# 09_Misc.net
KiCad netlist of a schematic drawn in Altium Designer
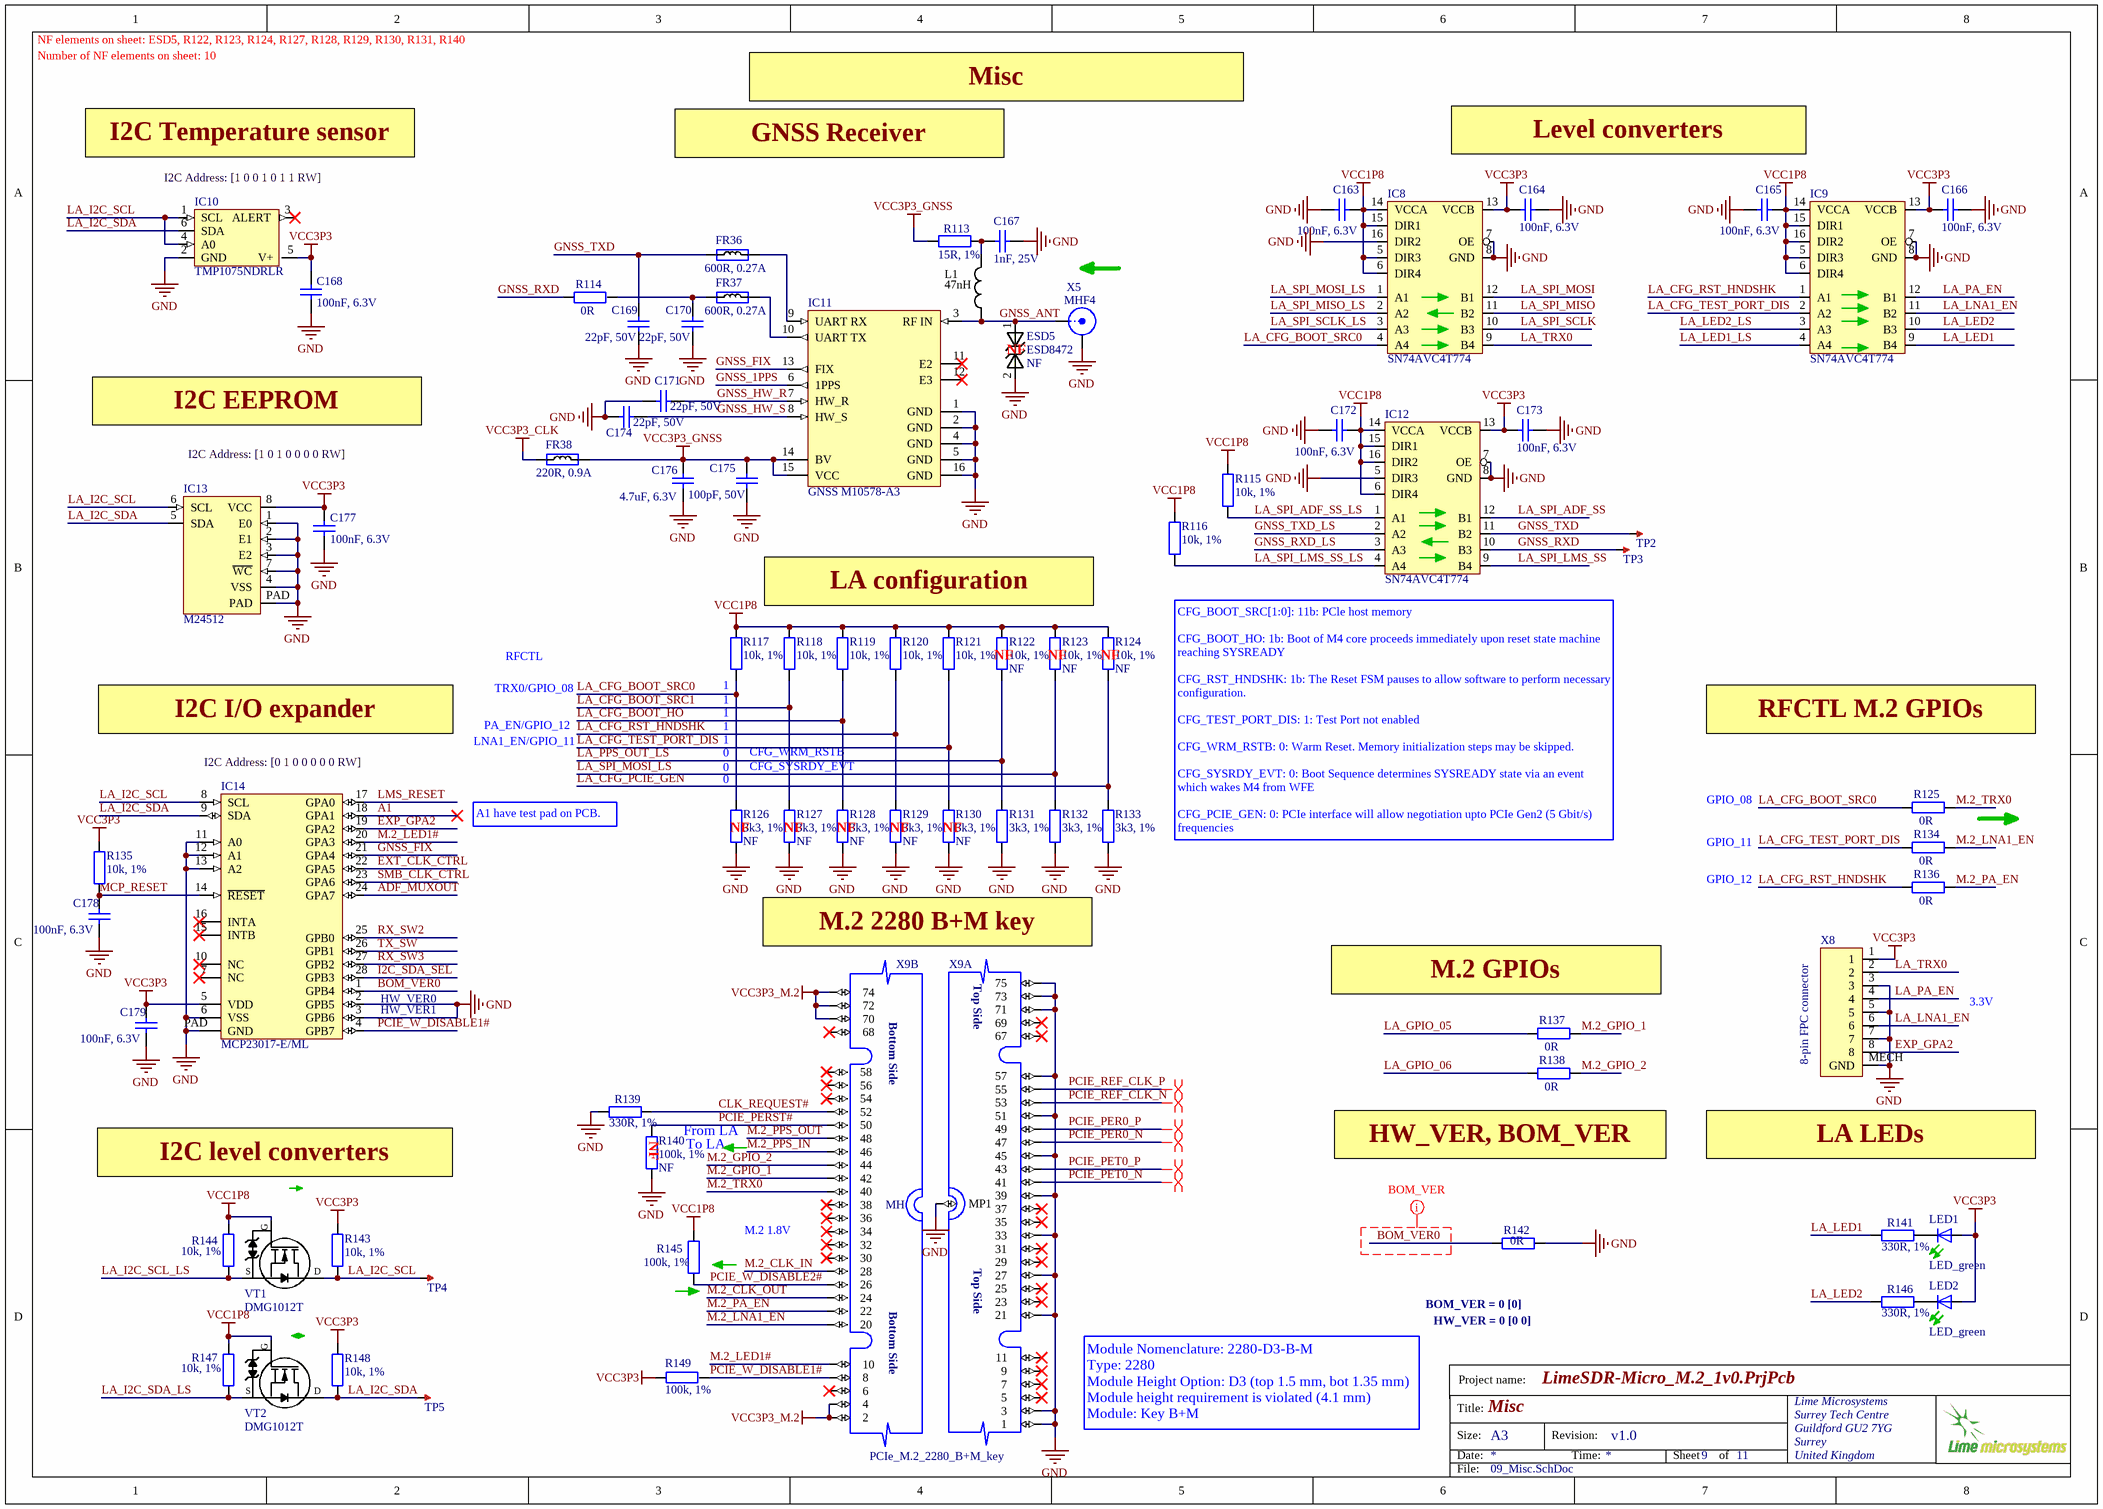
[diagram p0: 09_Misc.SchDoc]

(export (version "E")
  (design (tool "Eeschema 10.0.6"))
  (components
    (comp (ref "C163")
      (value "100nF, 6.3V")
      (footprint "CAP0201")
      (fields (field (name "MANUFACTURER") "Samsung") (field (name "TOLERANCE") "20%"))
      (libsource (lib "LimeMicroAltiumLib_schLib") (part "Cap_0402"))
    )
    (comp (ref "C164")
      (value "100nF, 6.3V")
      (footprint "CAP0201")
      (fields (field (name "MANUFACTURER") "Samsung") (field (name "TOLERANCE") "20%"))
      (libsource (lib "LimeMicroAltiumLib_schLib") (part "Cap_0402"))
    )
    (comp (ref "C165")
      (value "100nF, 6.3V")
      (footprint "CAP0201")
      (fields (field (name "MANUFACTURER") "Samsung") (field (name "TOLERANCE") "20%"))
      (libsource (lib "LimeMicroAltiumLib_schLib") (part "Cap_0402"))
    )
    (comp (ref "C166")
      (value "100nF, 6.3V")
      (footprint "CAP0201")
      (fields (field (name "MANUFACTURER") "Samsung") (field (name "TOLERANCE") "20%"))
      (libsource (lib "LimeMicroAltiumLib_schLib") (part "Cap_0402"))
    )
    (comp (ref "C167")
      (value "1nF, 25V")
      (footprint "CAP0201")
      (fields (field (name "TOLERANCE") "±10%") (field (name "MANUFACTURER") "TDK Corporation"))
      (libsource (lib "LimeMicroAltiumLib_schLib") (part "Cap_0402"))
    )
    (comp (ref "C168")
      (value "100nF, 6.3V")
      (footprint "CAP0201")
      (fields (field (name "MANUFACTURER") "Samsung") (field (name "TOLERANCE") "20%"))
      (libsource (lib "LimeMicroAltiumLib_schLib") (part "Cap_0402"))
    )
    (comp (ref "C169")
      (value "22pF, 50V")
      (footprint "CAP0201")
      (fields
        (field (name "MANUFACTURER") "Murata")
        (field (name "TOLERANCE") "5%")
        (field (name "VOLTAGE") "50V")
      )
      (libsource (lib "LimeMicroAltiumLib_schLib") (part "Cap_0402"))
    )
    (comp (ref "C170")
      (value "22pF, 50V")
      (footprint "CAP0201")
      (fields
        (field (name "MANUFACTURER") "Murata")
        (field (name "TOLERANCE") "5%")
        (field (name "VOLTAGE") "50V")
      )
      (libsource (lib "LimeMicroAltiumLib_schLib") (part "Cap_0402"))
    )
    (comp (ref "C171")
      (value "22pF, 50V")
      (footprint "CAP0201")
      (fields
        (field (name "MANUFACTURER") "Murata")
        (field (name "TOLERANCE") "5%")
        (field (name "VOLTAGE") "50V")
      )
      (libsource (lib "LimeMicroAltiumLib_schLib") (part "Cap_0402"))
    )
    (comp (ref "C172")
      (value "100nF, 6.3V")
      (footprint "CAP0201")
      (fields (field (name "MANUFACTURER") "Samsung") (field (name "TOLERANCE") "20%"))
      (libsource (lib "LimeMicroAltiumLib_schLib") (part "Cap_0402"))
    )
    (comp (ref "C173")
      (value "100nF, 6.3V")
      (footprint "CAP0201")
      (fields (field (name "MANUFACTURER") "Samsung") (field (name "TOLERANCE") "20%"))
      (libsource (lib "LimeMicroAltiumLib_schLib") (part "Cap_0402"))
    )
    (comp (ref "C174")
      (value "22pF, 50V")
      (footprint "CAP0201")
      (fields
        (field (name "MANUFACTURER") "Murata")
        (field (name "TOLERANCE") "5%")
        (field (name "VOLTAGE") "50V")
      )
      (libsource (lib "LimeMicroAltiumLib_schLib") (part "Cap_0402"))
    )
    (comp (ref "C175")
      (value "100pF, 50V")
      (footprint "CAP0201")
      (fields
        (field (name "MANUFACTURER") "TDK")
        (field (name "TOLERANCE") "5%")
        (field (name "VOLTAGE") "50V")
      )
      (libsource (lib "LimeMicroAltiumLib_schLib") (part "Cap_0402"))
    )
    (comp (ref "C176")
      (value "4.7uF, 6.3V")
      (footprint "CAP0402")
      (fields
        (field (name "MANUFACTURER") "Murata Electronics North America")
        (field (name "TOLERANCE") "±20%")
      )
      (libsource (lib "LimeMicroAltiumLib_schLib") (part "Cap_0402"))
    )
    (comp (ref "C177")
      (value "100nF, 6.3V")
      (footprint "CAP0201")
      (fields (field (name "MANUFACTURER") "Samsung") (field (name "TOLERANCE") "20%"))
      (libsource (lib "LimeMicroAltiumLib_schLib") (part "Cap_0402"))
    )
    (comp (ref "C178")
      (value "100nF, 6.3V")
      (footprint "CAP0201")
      (fields (field (name "MANUFACTURER") "Samsung") (field (name "TOLERANCE") "20%"))
      (libsource (lib "LimeMicroAltiumLib_schLib") (part "Cap_0402"))
    )
    (comp (ref "C179")
      (value "100nF, 6.3V")
      (footprint "CAP0201")
      (fields (field (name "MANUFACTURER") "Samsung") (field (name "TOLERANCE") "20%"))
      (libsource (lib "LimeMicroAltiumLib_schLib") (part "Cap_0402"))
    )
    (comp (ref "ESD5")
      (value "ESD8472")
      (footprint "ESD8472_X3DFN2")
      (fields (field (name "MANUFACTURER") "ON Semiconductor") (field (name "ASSEMBLY INFO") "NF"))
      (libsource (lib "LimeMicroAltiumLib_schLib") (part "ESD8472"))
    )
    (comp (ref "FR36")
      (value "600R, 0.27A")
      (footprint "RES0201")
      (fields (field (name "MANUFACTURER") "Taiyo Yuden"))
      (libsource (lib "LimeMicroAltiumLib_schLib") (part "Ferrite"))
    )
    (comp (ref "FR37")
      (value "600R, 0.27A")
      (footprint "RES0201")
      (fields (field (name "MANUFACTURER") "Taiyo Yuden"))
      (libsource (lib "LimeMicroAltiumLib_schLib") (part "Ferrite"))
    )
    (comp (ref "FR38")
      (value "220R, 0.9A")
      (footprint "RES0402")
      (fields (field (name "MANUFACTURER") "TDK Corporation"))
      (libsource (lib "LimeFPGAboard_schLib") (part "Ferrite"))
    )
    (comp (ref "IC8")
      (value "SN74AVC4T774")
      (footprint "SN74AVC4T774_v1")
      (fields (field (name "MANUFACTURER") "Texas Instruments"))
      (libsource (lib "LimeMicroAltiumLib") (part "SN74AVC4T774"))
    )
    (comp (ref "IC9")
      (value "SN74AVC4T774")
      (footprint "SN74AVC4T774_v1")
      (fields (field (name "MANUFACTURER") "Texas Instruments"))
      (libsource (lib "LimeMicroAltiumLib") (part "SN74AVC4T774"))
    )
    (comp (ref "IC10")
      (value "TMP1075NDRLR")
      (footprint "TMP1075NDRLR_temperature_sensor_SOT563")
      (fields (field (name "MANUFACTURER") "Texas Instruments"))
      (libsource (lib "LimeMicroAltiumLib_schLib_r04") (part "TMP1075NDRLR_temperature_sensor"))
    )
    (comp (ref "IC11")
      (value "GNSS M10578-A3")
      (footprint "M10578-A3_v2")
      (fields (field (name "MANUFACTURER") "Antenova"))
      (libsource (lib "LimeMicroAltiumLib_schLib_r04") (part "M10578-A3_GPS_GNSS"))
    )
    (comp (ref "IC12")
      (value "SN74AVC4T774")
      (footprint "SN74AVC4T774_v1")
      (fields (field (name "MANUFACTURER") "Texas Instruments"))
      (libsource (lib "LimeMicroAltiumLib") (part "SN74AVC4T774"))
    )
    (comp (ref "IC13")
      (value "M24512")
      (footprint "M24128-DFMC6TG")
      (fields (field (name "MANUFACTURER") "STMicroelectronics"))
      (libsource (lib "LimeMicroAltiumLib_schLib") (part "M24128-DFMC6TG"))
    )
    (comp (ref "IC14")
      (value "MCP23017-E/ML")
      (footprint "MCP23017-E/ML_QFN28")
      (fields (field (name "MANUFACTURER") "Microchip"))
      (libsource (lib "LimeMicroAltiumLib") (part "MCP23017-E/ML_I2C_expander"))
    )
    (comp (ref "L1")
      (value "47nH")
      (footprint "RES0402")
      (fields
        (field (name "MANUFACTURER") "COILCRAFT")
        (field (name "MANUFACTURER PART NUMBER") "0402HP-47NXJLU")
      )
      (libsource (lib "LimeMicroAltiumLib_schLib") (part "Inductor_0603"))
    )
    (comp (ref "LED1")
      (value "LED_green")
      (footprint "LED0201")
      (fields (field (name "MANUFACTURER") "Kingbright"))
      (libsource (lib "LimeFPGAboard_schLib") (part "LED_green"))
    )
    (comp (ref "LED2")
      (value "LED_green")
      (footprint "LED0201")
      (fields (field (name "MANUFACTURER") "Kingbright"))
      (libsource (lib "LimeFPGAboard_schLib") (part "LED_green"))
    )
    (comp (ref "R113")
      (value "15R, 1%")
      (footprint "RES0201")
      (fields (field (name "MANUFACTURER") "Yageo") (field (name "TOLERANCE") "1%"))
      (libsource (lib "LimeFPGAboard_schLib") (part "Res_0402"))
    )
    (comp (ref "R114")
      (value "0R")
      (footprint "RES0201")
      (fields (field (name "MANUFACTURER") "Yageo") (field (name "TOLERANCE") "5%"))
      (libsource (lib "LimeFPGAboard_schLib") (part "Res_0402"))
    )
    (comp (ref "R115")
      (value "10k, 1%")
      (footprint "RES0201")
      (fields (field (name "MANUFACTURER") "Yageo") (field (name "TOLERANCE") "1%"))
      (libsource (lib "LimeFPGAboard_schLib") (part "Res_0402"))
    )
    (comp (ref "R116")
      (value "10k, 1%")
      (footprint "RES0201")
      (fields (field (name "MANUFACTURER") "Yageo") (field (name "TOLERANCE") "1%"))
      (libsource (lib "LimeFPGAboard_schLib") (part "Res_0402"))
    )
    (comp (ref "R117")
      (value "10k, 1%")
      (footprint "RES0201")
      (fields (field (name "MANUFACTURER") "Yageo") (field (name "TOLERANCE") "1%"))
      (libsource (lib "LimeFPGAboard_schLib") (part "Res_0402"))
    )
    (comp (ref "R118")
      (value "10k, 1%")
      (footprint "RES0201")
      (fields (field (name "MANUFACTURER") "Yageo") (field (name "TOLERANCE") "1%"))
      (libsource (lib "LimeFPGAboard_schLib") (part "Res_0402"))
    )
    (comp (ref "R119")
      (value "10k, 1%")
      (footprint "RES0201")
      (fields (field (name "MANUFACTURER") "Yageo") (field (name "TOLERANCE") "1%"))
      (libsource (lib "LimeFPGAboard_schLib") (part "Res_0402"))
    )
    (comp (ref "R120")
      (value "10k, 1%")
      (footprint "RES0201")
      (fields (field (name "MANUFACTURER") "Yageo") (field (name "TOLERANCE") "1%"))
      (libsource (lib "LimeFPGAboard_schLib") (part "Res_0402"))
    )
    (comp (ref "R121")
      (value "10k, 1%")
      (footprint "RES0201")
      (fields (field (name "MANUFACTURER") "Yageo") (field (name "TOLERANCE") "1%"))
      (libsource (lib "LimeFPGAboard_schLib") (part "Res_0402"))
    )
    (comp (ref "R122")
      (value "10k, 1%")
      (footprint "RES0201")
      (fields
        (field (name "ASSEMBLY INFO") "NF")
        (field (name "MANUFACTURER") "Yageo")
        (field (name "TOLERANCE") "1%")
      )
      (libsource (lib "LimeFPGAboard_schLib") (part "Res_0402"))
    )
    (comp (ref "R123")
      (value "10k, 1%")
      (footprint "RES0201")
      (fields
        (field (name "ASSEMBLY INFO") "NF")
        (field (name "MANUFACTURER") "Yageo")
        (field (name "TOLERANCE") "1%")
      )
      (libsource (lib "LimeFPGAboard_schLib") (part "Res_0402"))
    )
    (comp (ref "R124")
      (value "10k, 1%")
      (footprint "RES0201")
      (fields
        (field (name "ASSEMBLY INFO") "NF")
        (field (name "MANUFACTURER") "Yageo")
        (field (name "TOLERANCE") "1%")
      )
      (libsource (lib "LimeFPGAboard_schLib") (part "Res_0402"))
    )
    (comp (ref "R125")
      (value "0R")
      (footprint "RES0201")
      (fields (field (name "MANUFACTURER") "Yageo") (field (name "TOLERANCE") "5%"))
      (libsource (lib "LimeFPGAboard_schLib") (part "Res_0402"))
    )
    (comp (ref "R126")
      (value "3k3, 1%")
      (footprint "RES0201")
      (fields
        (field (name "ASSEMBLY INFO") "NF")
        (field (name "MANUFACTURER") "Yageo")
        (field (name "TOLERANCE") "1%")
      )
      (libsource (lib "LimeFPGAboard_schLib") (part "Res_0402"))
    )
    (comp (ref "R127")
      (value "3k3, 1%")
      (footprint "RES0201")
      (fields
        (field (name "ASSEMBLY INFO") "NF")
        (field (name "MANUFACTURER") "Yageo")
        (field (name "TOLERANCE") "1%")
      )
      (libsource (lib "LimeFPGAboard_schLib") (part "Res_0402"))
    )
    (comp (ref "R128")
      (value "3k3, 1%")
      (footprint "RES0201")
      (fields
        (field (name "ASSEMBLY INFO") "NF")
        (field (name "MANUFACTURER") "Yageo")
        (field (name "TOLERANCE") "1%")
      )
      (libsource (lib "LimeFPGAboard_schLib") (part "Res_0402"))
    )
    (comp (ref "R129")
      (value "3k3, 1%")
      (footprint "RES0201")
      (fields
        (field (name "ASSEMBLY INFO") "NF")
        (field (name "MANUFACTURER") "Yageo")
        (field (name "TOLERANCE") "1%")
      )
      (libsource (lib "LimeFPGAboard_schLib") (part "Res_0402"))
    )
    (comp (ref "R130")
      (value "3k3, 1%")
      (footprint "RES0201")
      (fields
        (field (name "ASSEMBLY INFO") "NF")
        (field (name "MANUFACTURER") "Yageo")
        (field (name "TOLERANCE") "1%")
      )
      (libsource (lib "LimeFPGAboard_schLib") (part "Res_0402"))
    )
    (comp (ref "R131")
      (value "3k3, 1%")
      (footprint "RES0201")
      (fields (field (name "MANUFACTURER") "Yageo") (field (name "TOLERANCE") "1%"))
      (libsource (lib "LimeFPGAboard_schLib") (part "Res_0402"))
    )
    (comp (ref "R132")
      (value "3k3, 1%")
      (footprint "RES0201")
      (fields (field (name "MANUFACTURER") "Yageo") (field (name "TOLERANCE") "1%"))
      (libsource (lib "LimeFPGAboard_schLib") (part "Res_0402"))
    )
    (comp (ref "R133")
      (value "3k3, 1%")
      (footprint "RES0201")
      (fields (field (name "MANUFACTURER") "Yageo") (field (name "TOLERANCE") "1%"))
      (libsource (lib "LimeFPGAboard_schLib") (part "Res_0402"))
    )
    (comp (ref "R134")
      (value "0R")
      (footprint "RES0201")
      (fields (field (name "MANUFACTURER") "Yageo") (field (name "TOLERANCE") "5%"))
      (libsource (lib "LimeFPGAboard_schLib") (part "Res_0402"))
    )
    (comp (ref "R135")
      (value "10k, 1%")
      (footprint "RES0201")
      (fields (field (name "MANUFACTURER") "Yageo") (field (name "TOLERANCE") "1%"))
      (libsource (lib "LimeFPGAboard_schLib") (part "Res_0402"))
    )
    (comp (ref "R136")
      (value "0R")
      (footprint "RES0201")
      (fields (field (name "MANUFACTURER") "Yageo") (field (name "TOLERANCE") "5%"))
      (libsource (lib "LimeFPGAboard_schLib") (part "Res_0402"))
    )
    (comp (ref "R137")
      (value "0R")
      (footprint "RES0201")
      (fields (field (name "MANUFACTURER") "Yageo") (field (name "TOLERANCE") "5%"))
      (libsource (lib "LimeFPGAboard_schLib") (part "Res_0402"))
    )
    (comp (ref "R138")
      (value "0R")
      (footprint "RES0201")
      (fields (field (name "MANUFACTURER") "Yageo") (field (name "TOLERANCE") "5%"))
      (libsource (lib "LimeFPGAboard_schLib") (part "Res_0402"))
    )
    (comp (ref "R139")
      (value "330R, 1%")
      (footprint "RES0201")
      (fields (field (name "MANUFACTURER") "Vishay Dale") (field (name "TOLERANCE") "1%"))
      (libsource (lib "LimeFPGAboard_schLib") (part "Res_0402"))
    )
    (comp (ref "R140")
      (value "100k, 1%")
      (footprint "RES0201")
      (fields
        (field (name "ASSEMBLY INFO") "NF")
        (field (name "MANUFACTURER") "Yageo")
        (field (name "TOLERANCE") "1%")
      )
      (libsource (lib "LimeMicroAltiumLib_schLib") (part "Res_0402"))
    )
    (comp (ref "R141")
      (value "330R, 1%")
      (footprint "RES0201")
      (fields (field (name "MANUFACTURER") "Vishay Dale") (field (name "TOLERANCE") "1%"))
      (libsource (lib "LimeFPGAboard_schLib") (part "Res_0402"))
    )
    (comp (ref "R142")
      (value "0R")
      (footprint "RES0201")
      (fields (field (name "MANUFACTURER") "Yageo") (field (name "TOLERANCE") "5%"))
      (libsource (lib "LimeFPGAboard_schLib") (part "Res_0402"))
    )
    (comp (ref "R143")
      (value "10k, 1%")
      (footprint "RES0201")
      (fields (field (name "MANUFACTURER") "Yageo") (field (name "TOLERANCE") "1%"))
      (libsource (lib "LimeFPGAboard_schLib") (part "Res_0402"))
    )
    (comp (ref "R144")
      (value "10k, 1%")
      (footprint "RES0201")
      (fields (field (name "MANUFACTURER") "Yageo") (field (name "TOLERANCE") "1%"))
      (libsource (lib "LimeFPGAboard_schLib") (part "Res_0402"))
    )
    (comp (ref "R145")
      (value "100k, 1%")
      (footprint "RES0201")
      (fields (field (name "MANUFACTURER") "Yageo") (field (name "TOLERANCE") "1%"))
      (libsource (lib "LimeMicroAltiumLib_schLib") (part "Res_0402"))
    )
    (comp (ref "R146")
      (value "330R, 1%")
      (footprint "RES0201")
      (fields (field (name "MANUFACTURER") "Vishay Dale") (field (name "TOLERANCE") "1%"))
      (libsource (lib "LimeFPGAboard_schLib") (part "Res_0402"))
    )
    (comp (ref "R147")
      (value "10k, 1%")
      (footprint "RES0201")
      (fields (field (name "MANUFACTURER") "Yageo") (field (name "TOLERANCE") "1%"))
      (libsource (lib "LimeFPGAboard_schLib") (part "Res_0402"))
    )
    (comp (ref "R148")
      (value "10k, 1%")
      (footprint "RES0201")
      (fields (field (name "MANUFACTURER") "Yageo") (field (name "TOLERANCE") "1%"))
      (libsource (lib "LimeFPGAboard_schLib") (part "Res_0402"))
    )
    (comp (ref "R149")
      (value "100k, 1%")
      (footprint "RES0201")
      (fields (field (name "MANUFACTURER") "Yageo") (field (name "TOLERANCE") "1%"))
      (libsource (lib "LimeMicroAltiumLib_schLib") (part "Res_0402"))
    )
    (comp (ref "TP2")
      (value "TESTPOINT_PAD")
      (footprint "TP_PAD_1MM")
      (description "Test Point PCB mount Miniature White")
      (libsource (lib "LimeMicroAltiumLib_schLib_r04") (part "TESTPOINT_PAD"))
    )
    (comp (ref "TP3")
      (value "TESTPOINT_PAD")
      (footprint "TP_PAD_1MM")
      (description "Test Point PCB mount Miniature White")
      (libsource (lib "LimeMicroAltiumLib_schLib_r04") (part "TESTPOINT_PAD"))
    )
    (comp (ref "TP4")
      (value "TESTPOINT_PAD")
      (footprint "TP_PAD_1MM")
      (description "Test Point PCB mount Miniature White")
      (libsource (lib "LimeMicroAltiumLib_schLib_r04") (part "TESTPOINT_PAD"))
    )
    (comp (ref "TP5")
      (value "TESTPOINT_PAD")
      (footprint "TP_PAD_1MM")
      (description "Test Point PCB mount Miniature White")
      (libsource (lib "LimeMicroAltiumLib_schLib_r04") (part "TESTPOINT_PAD"))
    )
    (comp (ref "VT1")
      (value "DMG1012T")
      (footprint "SOT523")
      (fields (field (name "MANUFACTURER") "Diodes Incorporated"))
      (libsource (lib "LimeMicroAltiumLib_schLib_r01") (part "DMG1012T"))
    )
    (comp (ref "VT2")
      (value "DMG1012T")
      (footprint "SOT523")
      (fields (field (name "MANUFACTURER") "Diodes Incorporated"))
      (libsource (lib "LimeMicroAltiumLib_schLib_r01") (part "DMG1012T"))
    )
    (comp (ref "X5")
      (value "MHF4")
      (footprint "IPEX_MHF4_conn")
      (description "IPEX MHF4 Connector Jack, Male Pin 50 Ohms Surface Mount Solder")
      (fields (field (name "MANUFACTURER") "TE Connectivity / Linx Technologies"))
      (libsource (lib "LimeMicroAltiumLib_schLib") (part "RF_IF_connector"))
    )
    (comp (ref "X8")
      (value "8-pin FPC connector")
      (footprint "503480-0800_8PIN_FPC_CONN")
      (fields (field (name "MANUFACTURER") "Molex"))
      (libsource (lib "LimeMicroAltiumLib_schLib_r04") (part "503480-0800_8PIN_FPC_CONN"))
    )
    (comp (ref "X9")
      (value "PCIe_M.2_2280_B+M_key")
      (footprint "PCIe_M.2_2280_B+M_key")
      (libsource (lib "LimeMicroAltiumLib") (part "PCIe_M.2_2280_B+M_key"))
    )
  )
  (nets
    (net (code "1") (name "/A1") (class "Default")
      (node (ref "IC14") (pin "18") (pinfunction "GPA1_18") (pintype "bidirectional+no_connect"))
    )
    (net (code "2") (name "/ADF_MUXOUT") (class "Default")
      (node (ref "IC14") (pin "24") (pinfunction "GPA7_24") (pintype "bidirectional"))
    )
    (net (code "3") (name "/BOM_VER0") (class "Default")
      (node (ref "IC14") (pin "1") (pinfunction "GPB4_1") (pintype "bidirectional"))
      (node (ref "R142") (pin "1") (pinfunction "1_1") (pintype "passive"))
    )
    (net (code "4") (name "/CLK_REQUEST#") (class "Default")
      (node (ref "R139") (pin "1") (pinfunction "1_1") (pintype "passive"))
      (node (ref "X9") (pin "P52") (pinfunction "52_P52") (pintype "bidirectional"))
    )
    (net (code "5") (name "/EXP_GPA2") (class "Default")
      (node (ref "IC14") (pin "19") (pinfunction "GPA2_19") (pintype "bidirectional"))
      (node (ref "X8") (pin "8") (pinfunction "8_8") (pintype "passive"))
    )
    (net (code "6") (name "/EXT_CLK_CTRL") (class "Default")
      (node (ref "IC14") (pin "22") (pinfunction "GPA5_22") (pintype "bidirectional"))
    )
    (net (code "7") (name "/GNSS_1PPS") (class "Default")
      (node (ref "IC11") (pin "6") (pinfunction "1PPS_6") (pintype "output"))
    )
    (net (code "8") (name "/GNSS_ANT") (class "Default")
      (node (ref "ESD5") (pin "1") (pinfunction "1_1") (pintype "passive"))
      (node (ref "IC11") (pin "3") (pinfunction "RF_IN_3") (pintype "input"))
      (node (ref "L1") (pin "1") (pinfunction "1_1") (pintype "passive"))
      (node (ref "X5") (pin "1") (pinfunction "X_1") (pintype "passive"))
    )
    (net (code "9") (name "/GNSS_FIX") (class "Default")
      (node (ref "IC11") (pin "13") (pinfunction "FIX_13") (pintype "output"))
      (node (ref "IC14") (pin "21") (pinfunction "GPA4_21") (pintype "bidirectional"))
    )
    (net (code "10") (name "/GNSS_HW_R") (class "Default")
      (node (ref "C171") (pin "1") (pinfunction "1_1") (pintype "passive"))
      (node (ref "IC11") (pin "7") (pinfunction "HW_R_7") (pintype "input"))
    )
    (net (code "11") (name "/GNSS_HW_S") (class "Default")
      (node (ref "C174") (pin "1") (pinfunction "1_1") (pintype "passive"))
      (node (ref "IC11") (pin "8") (pinfunction "HW_S_8") (pintype "input"))
    )
    (net (code "12") (name "/GNSS_RXD") (class "Default")
      (node (ref "IC12") (pin "10") (pinfunction "B3_10") (pintype "passive"))
      (node (ref "R114") (pin "1") (pinfunction "1_1") (pintype "passive"))
      (node (ref "TP3") (pin "1") (pintype "passive"))
    )
    (net (code "13") (name "/GNSS_RXD_LS") (class "Default")
      (node (ref "IC12") (pin "3") (pinfunction "A3_3") (pintype "passive"))
    )
    (net (code "14") (name "/GNSS_TXD") (class "Default")
      (node (ref "C169") (pin "1") (pinfunction "1_1") (pintype "passive"))
      (node (ref "FR36") (pin "1") (pinfunction "1_1") (pintype "passive"))
      (node (ref "IC12") (pin "11") (pinfunction "B2_11") (pintype "passive"))
      (node (ref "TP2") (pin "1") (pintype "passive"))
    )
    (net (code "15") (name "/GNSS_TXD_LS") (class "Default")
      (node (ref "IC12") (pin "2") (pinfunction "A2_2") (pintype "passive"))
    )
    (net (code "16") (name "/I2C_SDA_SEL") (class "Default")
      (node (ref "IC14") (pin "28") (pinfunction "GPB3_28") (pintype "bidirectional"))
    )
    (net (code "17") (name "/LA_CFG_BOOT_HO") (class "Default")
      (node (ref "R119") (pin "2") (pinfunction "2_2") (pintype "passive"))
      (node (ref "R128") (pin "1") (pinfunction "1_1") (pintype "passive"))
    )
    (net (code "18") (name "/LA_CFG_BOOT_SRC0") (class "Default")
      (node (ref "IC8") (pin "4") (pinfunction "A4_4") (pintype "passive"))
      (node (ref "R117") (pin "2") (pinfunction "2_2") (pintype "passive"))
      (node (ref "R125") (pin "1") (pinfunction "1_1") (pintype "passive"))
      (node (ref "R126") (pin "1") (pinfunction "1_1") (pintype "passive"))
    )
    (net (code "19") (name "/LA_CFG_BOOT_SRC1") (class "Default")
      (node (ref "R118") (pin "2") (pinfunction "2_2") (pintype "passive"))
      (node (ref "R127") (pin "1") (pinfunction "1_1") (pintype "passive"))
    )
    (net (code "20") (name "/LA_CFG_PCIE_GEN") (class "Default")
      (node (ref "R124") (pin "2") (pinfunction "2_2") (pintype "passive"))
      (node (ref "R133") (pin "1") (pinfunction "1_1") (pintype "passive"))
    )
    (net (code "21") (name "/LA_CFG_RST_HNDSHK") (class "Default")
      (node (ref "IC9") (pin "1") (pinfunction "A1_1") (pintype "passive"))
      (node (ref "R120") (pin "2") (pinfunction "2_2") (pintype "passive"))
      (node (ref "R129") (pin "1") (pinfunction "1_1") (pintype "passive"))
      (node (ref "R136") (pin "1") (pinfunction "1_1") (pintype "passive"))
    )
    (net (code "22") (name "/LA_CFG_TEST_PORT_DIS") (class "Default")
      (node (ref "IC9") (pin "2") (pinfunction "A2_2") (pintype "passive"))
      (node (ref "R121") (pin "2") (pinfunction "2_2") (pintype "passive"))
      (node (ref "R130") (pin "1") (pinfunction "1_1") (pintype "passive"))
      (node (ref "R134") (pin "1") (pinfunction "1_1") (pintype "passive"))
    )
    (net (code "23") (name "/LA_GPIO_05") (class "Default")
      (node (ref "R137") (pin "1") (pinfunction "1_1") (pintype "passive"))
    )
    (net (code "24") (name "/LA_GPIO_06") (class "Default")
      (node (ref "R138") (pin "1") (pinfunction "1_1") (pintype "passive"))
    )
    (net (code "25") (name "/LA_I2C_SCL") (class "Default")
      (node (ref "IC10") (pin "1") (pinfunction "SCL_1") (pintype "input"))
      (node (ref "IC10") (pin "4") (pinfunction "A0_4") (pintype "input"))
      (node (ref "IC13") (pin "6") (pinfunction "SCL_6") (pintype "input"))
      (node (ref "IC14") (pin "8") (pinfunction "SCL_8") (pintype "input"))
      (node (ref "R143") (pin "2") (pinfunction "2_2") (pintype "passive"))
      (node (ref "TP4") (pin "1") (pintype "passive"))
      (node (ref "VT1") (pin "D") (pinfunction "D_D") (pintype "passive"))
    )
    (net (code "26") (name "/LA_I2C_SCL_LS") (class "Default")
      (node (ref "R144") (pin "2") (pinfunction "2_2") (pintype "passive"))
      (node (ref "VT1") (pin "S") (pinfunction "S_S") (pintype "passive"))
    )
    (net (code "27") (name "/LA_I2C_SDA") (class "Default")
      (node (ref "IC10") (pin "6") (pinfunction "SDA_6") (pintype "bidirectional"))
      (node (ref "IC13") (pin "5") (pinfunction "SDA_5") (pintype "bidirectional"))
      (node (ref "IC14") (pin "9") (pinfunction "SDA_9") (pintype "bidirectional"))
      (node (ref "R148") (pin "2") (pinfunction "2_2") (pintype "passive"))
      (node (ref "TP5") (pin "1") (pintype "passive"))
      (node (ref "VT2") (pin "D") (pinfunction "D_D") (pintype "passive"))
    )
    (net (code "28") (name "/LA_I2C_SDA_LS") (class "Default")
      (node (ref "R147") (pin "2") (pinfunction "2_2") (pintype "passive"))
      (node (ref "VT2") (pin "S") (pinfunction "S_S") (pintype "passive"))
    )
    (net (code "29") (name "/LA_LED1") (class "Default")
      (node (ref "IC9") (pin "9") (pinfunction "B4_9") (pintype "passive"))
      (node (ref "R141") (pin "2") (pinfunction "2_2") (pintype "passive"))
    )
    (net (code "30") (name "/LA_LED1_LS") (class "Default")
      (node (ref "IC9") (pin "4") (pinfunction "A4_4") (pintype "passive"))
    )
    (net (code "31") (name "/LA_LED2") (class "Default")
      (node (ref "IC9") (pin "10") (pinfunction "B3_10") (pintype "passive"))
      (node (ref "R146") (pin "2") (pinfunction "2_2") (pintype "passive"))
    )
    (net (code "32") (name "/LA_LED2_LS") (class "Default")
      (node (ref "IC9") (pin "3") (pinfunction "A3_3") (pintype "passive"))
    )
    (net (code "33") (name "/LA_LNA1_EN") (class "Default")
      (node (ref "IC9") (pin "11") (pinfunction "B2_11") (pintype "passive"))
      (node (ref "X8") (pin "6") (pinfunction "6_6") (pintype "passive"))
    )
    (net (code "34") (name "/LA_PA_EN") (class "Default")
      (node (ref "IC9") (pin "12") (pinfunction "B1_12") (pintype "passive"))
      (node (ref "X8") (pin "4") (pinfunction "4_4") (pintype "passive"))
    )
    (net (code "35") (name "/LA_PPS_OUT_LS") (class "Default")
      (node (ref "R122") (pin "2") (pinfunction "2_2") (pintype "passive"))
      (node (ref "R131") (pin "1") (pinfunction "1_1") (pintype "passive"))
    )
    (net (code "36") (name "/LA_SPI_ADF_SS") (class "Default")
      (node (ref "IC12") (pin "12") (pinfunction "B1_12") (pintype "passive"))
    )
    (net (code "37") (name "/LA_SPI_ADF_SS_LS") (class "Default")
      (node (ref "IC12") (pin "1") (pinfunction "A1_1") (pintype "passive"))
      (node (ref "R115") (pin "2") (pinfunction "2_2") (pintype "passive"))
    )
    (net (code "38") (name "/LA_SPI_LMS_SS") (class "Default")
      (node (ref "IC12") (pin "9") (pinfunction "B4_9") (pintype "passive"))
    )
    (net (code "39") (name "/LA_SPI_LMS_SS_LS") (class "Default")
      (node (ref "IC12") (pin "4") (pinfunction "A4_4") (pintype "passive"))
      (node (ref "R116") (pin "2") (pinfunction "2_2") (pintype "passive"))
    )
    (net (code "40") (name "/LA_SPI_MISO") (class "Default")
      (node (ref "IC8") (pin "11") (pinfunction "B2_11") (pintype "passive"))
    )
    (net (code "41") (name "/LA_SPI_MISO_LS") (class "Default")
      (node (ref "IC8") (pin "2") (pinfunction "A2_2") (pintype "passive"))
    )
    (net (code "42") (name "/LA_SPI_MOSI") (class "Default")
      (node (ref "IC8") (pin "12") (pinfunction "B1_12") (pintype "passive"))
    )
    (net (code "43") (name "/LA_SPI_MOSI_LS") (class "Default")
      (node (ref "IC8") (pin "1") (pinfunction "A1_1") (pintype "passive"))
      (node (ref "R123") (pin "2") (pinfunction "2_2") (pintype "passive"))
      (node (ref "R132") (pin "1") (pinfunction "1_1") (pintype "passive"))
    )
    (net (code "44") (name "/LA_SPI_SCLK") (class "Default")
      (node (ref "IC8") (pin "10") (pinfunction "B3_10") (pintype "passive"))
    )
    (net (code "45") (name "/LA_SPI_SCLK_LS") (class "Default")
      (node (ref "IC8") (pin "3") (pinfunction "A3_3") (pintype "passive"))
    )
    (net (code "46") (name "/LA_TRX0") (class "Default")
      (node (ref "IC8") (pin "9") (pinfunction "B4_9") (pintype "passive"))
      (node (ref "X8") (pin "2") (pinfunction "2_2") (pintype "passive"))
    )
    (net (code "47") (name "/LMS_RESET") (class "Default")
      (node (ref "IC14") (pin "17") (pinfunction "GPA0_17") (pintype "bidirectional"))
    )
    (net (code "48") (name "/M.2_CLK_IN") (class "Default")
      (node (ref "X9") (pin "P28") (pinfunction "28_P28") (pintype "bidirectional"))
    )
    (net (code "49") (name "/M.2_CLK_OUT") (class "Default")
      (node (ref "X9") (pin "P24") (pinfunction "24_P24") (pintype "bidirectional"))
    )
    (net (code "50") (name "/M.2_GPIO_1") (class "Default")
      (node (ref "R137") (pin "2") (pinfunction "2_2") (pintype "passive"))
      (node (ref "X9") (pin "P42") (pinfunction "42_P42") (pintype "bidirectional"))
    )
    (net (code "51") (name "/M.2_GPIO_2") (class "Default")
      (node (ref "R138") (pin "2") (pinfunction "2_2") (pintype "passive"))
      (node (ref "X9") (pin "P44") (pinfunction "44_P44") (pintype "bidirectional"))
    )
    (net (code "52") (name "/M.2_LED1#") (class "Default")
      (node (ref "IC14") (pin "20") (pinfunction "GPA3_20") (pintype "bidirectional"))
      (node (ref "X9") (pin "P10") (pinfunction "10_P10") (pintype "bidirectional"))
    )
    (net (code "53") (name "/M.2_LNA1_EN") (class "Default")
      (node (ref "R134") (pin "2") (pinfunction "2_2") (pintype "passive"))
      (node (ref "X9") (pin "P20") (pinfunction "20_P20") (pintype "bidirectional"))
    )
    (net (code "54") (name "/M.2_PA_EN") (class "Default")
      (node (ref "R136") (pin "2") (pinfunction "2_2") (pintype "passive"))
      (node (ref "X9") (pin "P22") (pinfunction "22_P22") (pintype "bidirectional"))
    )
    (net (code "55") (name "/M.2_PPS_IN") (class "Default")
      (node (ref "X9") (pin "P46") (pinfunction "46_P46") (pintype "bidirectional"))
    )
    (net (code "56") (name "/M.2_PPS_OUT") (class "Default")
      (node (ref "X9") (pin "P48") (pinfunction "48_P48") (pintype "bidirectional"))
    )
    (net (code "57") (name "/M.2_TRX0") (class "Default")
      (node (ref "R125") (pin "2") (pinfunction "2_2") (pintype "passive"))
      (node (ref "X9") (pin "P40") (pinfunction "40_P40") (pintype "bidirectional"))
    )
    (net (code "58") (name "/MCP_RESET") (class "Default")
      (node (ref "C178") (pin "1") (pinfunction "1_1") (pintype "passive"))
      (node (ref "IC14") (pin "14") (pinfunction "~{RESET}_14") (pintype "input"))
      (node (ref "R135") (pin "2") (pinfunction "2_2") (pintype "passive"))
    )
    (net (code "59") (name "/PCIE_PER0_N") (class "Default")
      (node (ref "X9") (pin "P47") (pinfunction "47_P47") (pintype "bidirectional"))
    )
    (net (code "60") (name "/PCIE_PER0_P") (class "Default")
      (node (ref "X9") (pin "P49") (pinfunction "49_P49") (pintype "bidirectional"))
    )
    (net (code "61") (name "/PCIE_PERST#") (class "Default")
      (node (ref "R140") (pin "2") (pinfunction "2_2") (pintype "passive"))
      (node (ref "X9") (pin "P50") (pinfunction "50_P50") (pintype "bidirectional"))
    )
    (net (code "62") (name "/PCIE_PET0_N") (class "Default")
      (node (ref "X9") (pin "P41") (pinfunction "41_P41") (pintype "bidirectional"))
    )
    (net (code "63") (name "/PCIE_PET0_P") (class "Default")
      (node (ref "X9") (pin "P43") (pinfunction "43_P43") (pintype "bidirectional"))
    )
    (net (code "64") (name "/PCIE_REF_CLK_N") (class "Default")
      (node (ref "X9") (pin "P53") (pinfunction "53_P53") (pintype "bidirectional"))
    )
    (net (code "65") (name "/PCIE_REF_CLK_P") (class "Default")
      (node (ref "X9") (pin "P55") (pinfunction "55_P55") (pintype "bidirectional"))
    )
    (net (code "66") (name "/PCIE_W_DISABLE1#") (class "Default")
      (node (ref "IC14") (pin "4") (pinfunction "GPB7_4") (pintype "bidirectional"))
      (node (ref "R149") (pin "2") (pinfunction "2_2") (pintype "passive"))
      (node (ref "X9") (pin "P8") (pinfunction "8_P8") (pintype "bidirectional"))
    )
    (net (code "67") (name "/PCIE_W_DISABLE2#") (class "Default")
      (node (ref "R145") (pin "2") (pinfunction "2_2") (pintype "passive"))
      (node (ref "X9") (pin "P26") (pinfunction "26_P26") (pintype "bidirectional"))
    )
    (net (code "68") (name "/RX_SW2") (class "Default")
      (node (ref "IC14") (pin "25") (pinfunction "GPB0_25") (pintype "bidirectional"))
    )
    (net (code "69") (name "/RX_SW3") (class "Default")
      (node (ref "IC14") (pin "27") (pinfunction "GPB2_27") (pintype "bidirectional"))
    )
    (net (code "70") (name "/SMB_CLK_CTRL") (class "Default")
      (node (ref "IC14") (pin "23") (pinfunction "GPA6_23") (pintype "bidirectional"))
    )
    (net (code "71") (name "/TX_SW") (class "Default")
      (node (ref "IC14") (pin "26") (pinfunction "GPB1_26") (pintype "bidirectional"))
    )
    (net (code "72") (name "GND") (class "Default")
      (node (ref "C163") (pin "1") (pinfunction "1_1") (pintype "passive"))
      (node (ref "C164") (pin "2") (pinfunction "2_2") (pintype "passive"))
      (node (ref "C165") (pin "1") (pinfunction "1_1") (pintype "passive"))
      (node (ref "C166") (pin "2") (pinfunction "2_2") (pintype "passive"))
      (node (ref "C167") (pin "2") (pinfunction "2_2") (pintype "passive"))
      (node (ref "C168") (pin "2") (pinfunction "2_2") (pintype "passive"))
      (node (ref "C169") (pin "2") (pinfunction "2_2") (pintype "passive"))
      (node (ref "C170") (pin "2") (pinfunction "2_2") (pintype "passive"))
      (node (ref "C171") (pin "2") (pinfunction "2_2") (pintype "passive"))
      (node (ref "C172") (pin "1") (pinfunction "1_1") (pintype "passive"))
      (node (ref "C173") (pin "2") (pinfunction "2_2") (pintype "passive"))
      (node (ref "C174") (pin "2") (pinfunction "2_2") (pintype "passive"))
      (node (ref "C175") (pin "1") (pinfunction "1_1") (pintype "passive"))
      (node (ref "C176") (pin "1") (pinfunction "1_1") (pintype "passive"))
      (node (ref "C177") (pin "2") (pinfunction "2_2") (pintype "passive"))
      (node (ref "C178") (pin "2") (pinfunction "2_2") (pintype "passive"))
      (node (ref "C179") (pin "2") (pinfunction "2_2") (pintype "passive"))
      (node (ref "ESD5") (pin "2") (pinfunction "2_2") (pintype "passive"))
      (node (ref "IC10") (pin "2") (pinfunction "GND_2") (pintype "passive"))
      (node (ref "IC11") (pin "1") (pinfunction "GND_1") (pintype "passive"))
      (node (ref "IC11") (pin "16") (pinfunction "GND_16") (pintype "passive"))
      (node (ref "IC11") (pin "2") (pinfunction "GND_2") (pintype "passive"))
      (node (ref "IC11") (pin "4") (pinfunction "GND_4") (pintype "passive"))
      (node (ref "IC11") (pin "5") (pinfunction "GND_5") (pintype "passive"))
      (node (ref "IC12") (pin "5") (pinfunction "DIR3_5") (pintype "passive"))
      (node (ref "IC12") (pin "7") (pinfunction "OE_7") (pintype "passive"))
      (node (ref "IC12") (pin "8") (pinfunction "GND_8") (pintype "passive"))
      (node (ref "IC13") (pin "1") (pinfunction "E0_1") (pintype "input"))
      (node (ref "IC13") (pin "2") (pinfunction "E1_2") (pintype "input"))
      (node (ref "IC13") (pin "3") (pinfunction "E2_3") (pintype "input"))
      (node (ref "IC13") (pin "4") (pinfunction "VSS_4") (pintype "power_in"))
      (node (ref "IC13") (pin "7") (pinfunction "~{WC}_7") (pintype "input"))
      (node (ref "IC13") (pin "PAD") (pinfunction "PAD_PAD") (pintype "power_in"))
      (node (ref "IC14") (pin "11") (pinfunction "A0_11") (pintype "input"))
      (node (ref "IC14") (pin "12") (pinfunction "A1_12") (pintype "input"))
      (node (ref "IC14") (pin "13") (pinfunction "A2_13") (pintype "input"))
      (node (ref "IC14") (pin "2") (pinfunction "GPB5_2") (pintype "bidirectional"))
      (node (ref "IC14") (pin "3") (pinfunction "GPB6_3") (pintype "bidirectional"))
      (node (ref "IC14") (pin "6") (pinfunction "VSS_6") (pintype "power_in"))
      (node (ref "IC14") (pin "PAD") (pinfunction "GND_PAD") (pintype "passive"))
      (node (ref "IC8") (pin "16") (pinfunction "DIR2_16") (pintype "passive"))
      (node (ref "IC8") (pin "7") (pinfunction "OE_7") (pintype "passive"))
      (node (ref "IC8") (pin "8") (pinfunction "GND_8") (pintype "passive"))
      (node (ref "IC9") (pin "7") (pinfunction "OE_7") (pintype "passive"))
      (node (ref "IC9") (pin "8") (pinfunction "GND_8") (pintype "passive"))
      (node (ref "R126") (pin "2") (pinfunction "2_2") (pintype "passive"))
      (node (ref "R127") (pin "2") (pinfunction "2_2") (pintype "passive"))
      (node (ref "R128") (pin "2") (pinfunction "2_2") (pintype "passive"))
      (node (ref "R129") (pin "2") (pinfunction "2_2") (pintype "passive"))
      (node (ref "R130") (pin "2") (pinfunction "2_2") (pintype "passive"))
      (node (ref "R131") (pin "2") (pinfunction "2_2") (pintype "passive"))
      (node (ref "R132") (pin "2") (pinfunction "2_2") (pintype "passive"))
      (node (ref "R133") (pin "2") (pinfunction "2_2") (pintype "passive"))
      (node (ref "R139") (pin "2") (pinfunction "2_2") (pintype "passive"))
      (node (ref "R140") (pin "1") (pinfunction "1_1") (pintype "passive"))
      (node (ref "R142") (pin "2") (pinfunction "2_2") (pintype "passive"))
      (node (ref "X5") (pin "2") (pinfunction "Y_2") (pintype "passive"))
      (node (ref "X8") (pin "3") (pinfunction "3_3") (pintype "passive"))
      (node (ref "X8") (pin "5") (pinfunction "5_5") (pintype "passive"))
      (node (ref "X8") (pin "7") (pinfunction "7_7") (pintype "passive"))
      (node (ref "X8") (pin "MECH") (pinfunction "GND_MECH") (pintype "passive"))
      (node (ref "X9") (pin "MOUNTING-HOLE") (pinfunction "MP1_MOUNTING-HOLE") (pintype "bidirectional"))
      (node (ref "X9") (pin "P1") (pinfunction "1_P1") (pintype "bidirectional"))
      (node (ref "X9") (pin "P21") (pinfunction "21_P21") (pintype "bidirectional"))
      (node (ref "X9") (pin "P27") (pinfunction "27_P27") (pintype "bidirectional"))
      (node (ref "X9") (pin "P3") (pinfunction "3_P3") (pintype "bidirectional"))
      (node (ref "X9") (pin "P33") (pinfunction "33_P33") (pintype "bidirectional"))
      (node (ref "X9") (pin "P39") (pinfunction "39_P39") (pintype "bidirectional"))
      (node (ref "X9") (pin "P45") (pinfunction "45_P45") (pintype "bidirectional"))
      (node (ref "X9") (pin "P51") (pinfunction "51_P51") (pintype "bidirectional"))
      (node (ref "X9") (pin "P57") (pinfunction "57_P57") (pintype "bidirectional"))
      (node (ref "X9") (pin "P71") (pinfunction "71_P71") (pintype "bidirectional"))
      (node (ref "X9") (pin "P73") (pinfunction "73_P73") (pintype "bidirectional"))
      (node (ref "X9") (pin "P75") (pinfunction "75_P75") (pintype "bidirectional"))
    )
    (net (code "73") (name "Net-(C167-Pad1)") (class "Default")
      (node (ref "C167") (pin "1") (pinfunction "1_1") (pintype "passive"))
      (node (ref "L1") (pin "2") (pinfunction "2_2") (pintype "passive"))
      (node (ref "R113") (pin "1") (pinfunction "1_1") (pintype "passive"))
    )
    (net (code "74") (name "Net-(C170-Pad1)") (class "Default")
      (node (ref "C170") (pin "1") (pinfunction "1_1") (pintype "passive"))
      (node (ref "FR37") (pin "1") (pinfunction "1_1") (pintype "passive"))
      (node (ref "R114") (pin "2") (pinfunction "2_2") (pintype "passive"))
    )
    (net (code "75") (name "Net-(IC11-UART_RX)") (class "Default")
      (node (ref "FR36") (pin "2") (pinfunction "2_2") (pintype "passive"))
      (node (ref "IC11") (pin "9") (pinfunction "UART_RX_9") (pintype "input"))
    )
    (net (code "76") (name "Net-(IC11-UART_TX)") (class "Default")
      (node (ref "FR37") (pin "2") (pinfunction "2_2") (pintype "passive"))
      (node (ref "IC11") (pin "10") (pinfunction "UART_TX_10") (pintype "output"))
    )
    (net (code "77") (name "Net-(LED1-C)") (class "Default")
      (node (ref "LED1") (pin "K") (pinfunction "C_K") (pintype "power_in"))
      (node (ref "R141") (pin "1") (pinfunction "1_1") (pintype "passive"))
    )
    (net (code "78") (name "Net-(LED2-C)") (class "Default")
      (node (ref "LED2") (pin "K") (pinfunction "C_K") (pintype "power_in"))
      (node (ref "R146") (pin "1") (pinfunction "1_1") (pintype "passive"))
    )
    (net (code "79") (name "VCC1P8") (class "Default")
      (node (ref "C163") (pin "2") (pinfunction "2_2") (pintype "passive"))
      (node (ref "C165") (pin "2") (pinfunction "2_2") (pintype "passive"))
      (node (ref "C172") (pin "2") (pinfunction "2_2") (pintype "passive"))
      (node (ref "IC12") (pin "14") (pinfunction "VCCA_14") (pintype "passive"))
      (node (ref "IC12") (pin "15") (pinfunction "DIR1_15") (pintype "passive"))
      (node (ref "IC12") (pin "16") (pinfunction "DIR2_16") (pintype "passive"))
      (node (ref "IC12") (pin "6") (pinfunction "DIR4_6") (pintype "passive"))
      (node (ref "IC8") (pin "14") (pinfunction "VCCA_14") (pintype "passive"))
      (node (ref "IC8") (pin "15") (pinfunction "DIR1_15") (pintype "passive"))
      (node (ref "IC8") (pin "5") (pinfunction "DIR3_5") (pintype "passive"))
      (node (ref "IC8") (pin "6") (pinfunction "DIR4_6") (pintype "passive"))
      (node (ref "IC9") (pin "14") (pinfunction "VCCA_14") (pintype "passive"))
      (node (ref "IC9") (pin "15") (pinfunction "DIR1_15") (pintype "passive"))
      (node (ref "IC9") (pin "16") (pinfunction "DIR2_16") (pintype "passive"))
      (node (ref "IC9") (pin "5") (pinfunction "DIR3_5") (pintype "passive"))
      (node (ref "IC9") (pin "6") (pinfunction "DIR4_6") (pintype "passive"))
      (node (ref "R115") (pin "1") (pinfunction "1_1") (pintype "passive"))
      (node (ref "R116") (pin "1") (pinfunction "1_1") (pintype "passive"))
      (node (ref "R117") (pin "1") (pinfunction "1_1") (pintype "passive"))
      (node (ref "R118") (pin "1") (pinfunction "1_1") (pintype "passive"))
      (node (ref "R119") (pin "1") (pinfunction "1_1") (pintype "passive"))
      (node (ref "R120") (pin "1") (pinfunction "1_1") (pintype "passive"))
      (node (ref "R121") (pin "1") (pinfunction "1_1") (pintype "passive"))
      (node (ref "R122") (pin "1") (pinfunction "1_1") (pintype "passive"))
      (node (ref "R123") (pin "1") (pinfunction "1_1") (pintype "passive"))
      (node (ref "R124") (pin "1") (pinfunction "1_1") (pintype "passive"))
      (node (ref "R144") (pin "1") (pinfunction "1_1") (pintype "passive"))
      (node (ref "R145") (pin "1") (pinfunction "1_1") (pintype "passive"))
      (node (ref "R147") (pin "1") (pinfunction "1_1") (pintype "passive"))
      (node (ref "VT1") (pin "G") (pinfunction "G_G") (pintype "passive"))
      (node (ref "VT2") (pin "G") (pinfunction "G_G") (pintype "passive"))
    )
    (net (code "80") (name "VCC3P3") (class "Default")
      (node (ref "C164") (pin "1") (pinfunction "1_1") (pintype "passive"))
      (node (ref "C166") (pin "1") (pinfunction "1_1") (pintype "passive"))
      (node (ref "C168") (pin "1") (pinfunction "1_1") (pintype "passive"))
      (node (ref "C173") (pin "1") (pinfunction "1_1") (pintype "passive"))
      (node (ref "C177") (pin "1") (pinfunction "1_1") (pintype "passive"))
      (node (ref "C179") (pin "1") (pinfunction "1_1") (pintype "passive"))
      (node (ref "IC10") (pin "5") (pinfunction "V+_5") (pintype "power_in"))
      (node (ref "IC12") (pin "13") (pinfunction "VCCB_13") (pintype "passive"))
      (node (ref "IC13") (pin "8") (pinfunction "VCC_8") (pintype "power_in"))
      (node (ref "IC14") (pin "5") (pinfunction "VDD_5") (pintype "power_in"))
      (node (ref "IC8") (pin "13") (pinfunction "VCCB_13") (pintype "passive"))
      (node (ref "IC9") (pin "13") (pinfunction "VCCB_13") (pintype "passive"))
      (node (ref "LED1") (pin "A") (pinfunction "A_A") (pintype "power_in"))
      (node (ref "LED2") (pin "A") (pinfunction "A_A") (pintype "power_in"))
      (node (ref "R135") (pin "1") (pinfunction "1_1") (pintype "passive"))
      (node (ref "R143") (pin "1") (pinfunction "1_1") (pintype "passive"))
      (node (ref "R148") (pin "1") (pinfunction "1_1") (pintype "passive"))
      (node (ref "R149") (pin "1") (pinfunction "1_1") (pintype "passive"))
      (node (ref "X8") (pin "1") (pinfunction "1_1") (pintype "passive"))
    )
    (net (code "81") (name "VCC3P3_CLK") (class "Default")
      (node (ref "FR38") (pin "1") (pinfunction "1_1") (pintype "passive"))
    )
    (net (code "82") (name "VCC3P3_GNSS") (class "Default")
      (node (ref "C175") (pin "2") (pinfunction "2_2") (pintype "passive"))
      (node (ref "C176") (pin "2") (pinfunction "2_2") (pintype "passive"))
      (node (ref "FR38") (pin "2") (pinfunction "2_2") (pintype "passive"))
      (node (ref "IC11") (pin "14") (pinfunction "BV_14") (pintype "power_in"))
      (node (ref "IC11") (pin "15") (pinfunction "VCC_15") (pintype "power_in"))
      (node (ref "R113") (pin "2") (pinfunction "2_2") (pintype "passive"))
    )
    (net (code "83") (name "VCC3P3_M.2") (class "Default")
      (node (ref "X9") (pin "P2") (pinfunction "2_P2") (pintype "bidirectional"))
      (node (ref "X9") (pin "P4") (pinfunction "4_P4") (pintype "bidirectional"))
      (node (ref "X9") (pin "P70") (pinfunction "70_P70") (pintype "bidirectional"))
      (node (ref "X9") (pin "P72") (pinfunction "72_P72") (pintype "bidirectional"))
      (node (ref "X9") (pin "P74") (pinfunction "74_P74") (pintype "bidirectional"))
    )
    (net (code "84") (name "unconnected-(IC10-ALERT-Pad3)") (class "Default")
      (node (ref "IC10") (pin "3") (pinfunction "ALERT_3") (pintype "output+no_connect"))
    )
    (net (code "85") (name "unconnected-(IC11-E2-Pad11)") (class "Default")
      (node (ref "IC11") (pin "11") (pinfunction "E2_11") (pintype "passive+no_connect"))
    )
    (net (code "86") (name "unconnected-(IC11-E3-Pad12)") (class "Default")
      (node (ref "IC11") (pin "12") (pinfunction "E3_12") (pintype "passive+no_connect"))
    )
    (net (code "87") (name "unconnected-(IC14-INTA-Pad16)") (class "Default")
      (node (ref "IC14") (pin "16") (pinfunction "INTA_16") (pintype "open_collector+no_connect"))
    )
    (net (code "88") (name "unconnected-(IC14-INTB-Pad15)") (class "Default")
      (node (ref "IC14") (pin "15") (pinfunction "INTB_15") (pintype "open_collector+no_connect"))
    )
    (net (code "89") (name "unconnected-(IC14-NC-Pad7)") (class "Default")
      (node (ref "IC14") (pin "7") (pinfunction "NC_7") (pintype "passive+no_connect"))
    )
    (net (code "90") (name "unconnected-(IC14-NC-Pad10)") (class "Default")
      (node (ref "IC14") (pin "10") (pinfunction "NC_10") (pintype "passive+no_connect"))
    )
    (net (code "91") (name "unconnected-(X9A-5-PadP5)") (class "Default")
      (node (ref "X9") (pin "P5") (pinfunction "5_P5") (pintype "bidirectional+no_connect"))
    )
    (net (code "92") (name "unconnected-(X9A-7-PadP7)") (class "Default")
      (node (ref "X9") (pin "P7") (pinfunction "7_P7") (pintype "bidirectional+no_connect"))
    )
    (net (code "93") (name "unconnected-(X9A-9-PadP9)") (class "Default")
      (node (ref "X9") (pin "P9") (pinfunction "9_P9") (pintype "bidirectional+no_connect"))
    )
    (net (code "94") (name "unconnected-(X9A-11-PadP11)") (class "Default")
      (node (ref "X9") (pin "P11") (pinfunction "11_P11") (pintype "bidirectional+no_connect"))
    )
    (net (code "95") (name "unconnected-(X9A-23-PadP23)") (class "Default")
      (node (ref "X9") (pin "P23") (pinfunction "23_P23") (pintype "bidirectional+no_connect"))
    )
    (net (code "96") (name "unconnected-(X9A-25-PadP25)") (class "Default")
      (node (ref "X9") (pin "P25") (pinfunction "25_P25") (pintype "bidirectional+no_connect"))
    )
    (net (code "97") (name "unconnected-(X9A-29-PadP29)") (class "Default")
      (node (ref "X9") (pin "P29") (pinfunction "29_P29") (pintype "bidirectional+no_connect"))
    )
    (net (code "98") (name "unconnected-(X9A-31-PadP31)") (class "Default")
      (node (ref "X9") (pin "P31") (pinfunction "31_P31") (pintype "bidirectional+no_connect"))
    )
    (net (code "99") (name "unconnected-(X9A-35-PadP35)") (class "Default")
      (node (ref "X9") (pin "P35") (pinfunction "35_P35") (pintype "bidirectional+no_connect"))
    )
    (net (code "100") (name "unconnected-(X9A-37-PadP37)") (class "Default")
      (node (ref "X9") (pin "P37") (pinfunction "37_P37") (pintype "bidirectional+no_connect"))
    )
    (net (code "101") (name "unconnected-(X9A-67-PadP67)") (class "Default")
      (node (ref "X9") (pin "P67") (pinfunction "67_P67") (pintype "bidirectional+no_connect"))
    )
    (net (code "102") (name "unconnected-(X9A-69-PadP69)") (class "Default")
      (node (ref "X9") (pin "P69") (pinfunction "69_P69") (pintype "bidirectional+no_connect"))
    )
    (net (code "103") (name "unconnected-(X9B-6-PadP6)") (class "Default")
      (node (ref "X9") (pin "P6") (pinfunction "6_P6") (pintype "bidirectional+no_connect"))
    )
    (net (code "104") (name "unconnected-(X9B-30-PadP30)") (class "Default")
      (node (ref "X9") (pin "P30") (pinfunction "30_P30") (pintype "bidirectional+no_connect"))
    )
    (net (code "105") (name "unconnected-(X9B-32-PadP32)") (class "Default")
      (node (ref "X9") (pin "P32") (pinfunction "32_P32") (pintype "bidirectional+no_connect"))
    )
    (net (code "106") (name "unconnected-(X9B-34-PadP34)") (class "Default")
      (node (ref "X9") (pin "P34") (pinfunction "34_P34") (pintype "bidirectional+no_connect"))
    )
    (net (code "107") (name "unconnected-(X9B-36-PadP36)") (class "Default")
      (node (ref "X9") (pin "P36") (pinfunction "36_P36") (pintype "bidirectional+no_connect"))
    )
    (net (code "108") (name "unconnected-(X9B-38-PadP38)") (class "Default")
      (node (ref "X9") (pin "P38") (pinfunction "38_P38") (pintype "bidirectional+no_connect"))
    )
    (net (code "109") (name "unconnected-(X9B-54-PadP54)") (class "Default")
      (node (ref "X9") (pin "P54") (pinfunction "54_P54") (pintype "bidirectional+no_connect"))
    )
    (net (code "110") (name "unconnected-(X9B-56-PadP56)") (class "Default")
      (node (ref "X9") (pin "P56") (pinfunction "56_P56") (pintype "bidirectional+no_connect"))
    )
    (net (code "111") (name "unconnected-(X9B-58-PadP58)") (class "Default")
      (node (ref "X9") (pin "P58") (pinfunction "58_P58") (pintype "bidirectional+no_connect"))
    )
    (net (code "112") (name "unconnected-(X9B-68-PadP68)") (class "Default")
      (node (ref "X9") (pin "P68") (pinfunction "68_P68") (pintype "bidirectional+no_connect"))
    )
  )
)
